# swd.net
KiCad netlist of a schematic drawn in Altium Designer
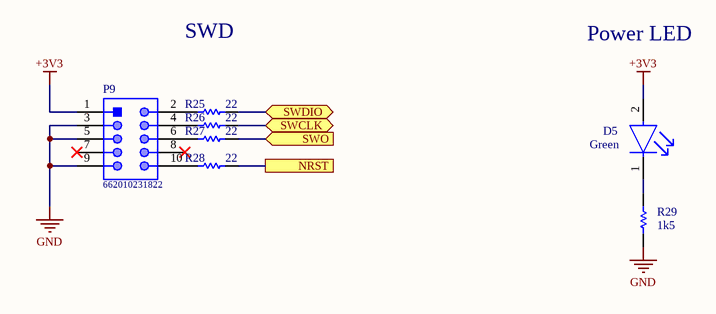
[diagram p0: swd.SchDoc]

(export (version "E")
  (design (tool "Eeschema 10.0.6"))
  (components
    (comp (ref "D5")
      (value "Green")
      (footprint "Led 0603")
      (description "LED 0805")
      (fields (field (name "VOLTAGE") "2V") (field (name "MANUFACTURER") "Vishay Lite-On"))
      (libsource (lib "F4_Flight_Controller") (part "LED 0805"))
    )
    (comp (ref "P9")
      (value "662010231822")
      (footprint "HDRV10W90P254_2X5_1270X483X840P")
      (description "SMT Male Header WR-MPC3, with SMT Solder Tabs, Vertical, Dual Row, pitch 3 mm, 10 pins")
      (fields (field (name "MANUFACTURER") "Wurth Electronics") (field (name "PUBLISHER") "WurthElektronik"))
      (libsource (lib "F4_Flight_Controller") (part "Male Header 02x05"))
    )
    (comp (ref "R25")
      (value "22")
      (footprint "Resistor 0402")
      (description "Chip Resistor 0402")
      (fields (field (name "MANUFACTURER") "Vishay") (field (name "PART NUMBER") "CRCW0402120RFKED"))
      (libsource (lib "F4_Flight_Controller") (part "Resistor 0402"))
    )
    (comp (ref "R26")
      (value "22")
      (footprint "Resistor 0402")
      (description "Chip Resistor 0402")
      (fields (field (name "MANUFACTURER") "Vishay") (field (name "PART NUMBER") "CRCW0402120RFKED"))
      (libsource (lib "F4_Flight_Controller") (part "Resistor 0402"))
    )
    (comp (ref "R27")
      (value "22")
      (footprint "Resistor 0402")
      (description "Chip Resistor 0402")
      (fields (field (name "MANUFACTURER") "Vishay") (field (name "PART NUMBER") "CRCW0402120RFKED"))
      (libsource (lib "F4_Flight_Controller") (part "Resistor 0402"))
    )
    (comp (ref "R28")
      (value "22")
      (footprint "Resistor 0402")
      (description "Chip Resistor 0402")
      (fields (field (name "MANUFACTURER") "Vishay") (field (name "PART NUMBER") "CRCW0402120RFKED"))
      (libsource (lib "F4_Flight_Controller") (part "Resistor 0402"))
    )
    (comp (ref "R29")
      (value "1k5")
      (footprint "RESISTOR 0603")
      (description "Chip Resistor 0603")
      (fields (field (name "MANUFACTURER") "Vishay") (field (name "PART NUMBER") "CRCW0402120RFKED"))
      (libsource (lib "F4_Flight_Controller") (part "Resistor 0603"))
    )
  )
  (nets
    (net (code "1") (name "+3V3") (class "Default")
      (node (ref "D5") (pin "2") (pinfunction "A_2") (pintype "passive"))
      (node (ref "P9") (pin "1") (pinfunction "1_1") (pintype "passive"))
    )
    (net (code "2") (name "/NRST") (class "Default")
      (node (ref "R28") (pin "1") (pinfunction "1_1") (pintype "passive"))
    )
    (net (code "3") (name "/SWCLK") (class "Default")
      (node (ref "R26") (pin "1") (pinfunction "1_1") (pintype "passive"))
    )
    (net (code "4") (name "/SWDIO") (class "Default")
      (node (ref "R25") (pin "1") (pinfunction "1_1") (pintype "passive"))
    )
    (net (code "5") (name "/SWO") (class "Default")
      (node (ref "R27") (pin "1") (pinfunction "1_1") (pintype "passive"))
    )
    (net (code "6") (name "GND") (class "Default")
      (node (ref "P9") (pin "3") (pinfunction "3_3") (pintype "passive"))
      (node (ref "P9") (pin "5") (pinfunction "5_5") (pintype "passive"))
      (node (ref "P9") (pin "9") (pinfunction "9_9") (pintype "passive"))
      (node (ref "R29") (pin "1") (pinfunction "1_1") (pintype "passive"))
    )
    (net (code "7") (name "Net-(D5-C)") (class "Default")
      (node (ref "D5") (pin "1") (pinfunction "C_1") (pintype "passive"))
      (node (ref "R29") (pin "2") (pinfunction "2_2") (pintype "passive"))
    )
    (net (code "8") (name "Net-(P9-Pad2)") (class "Default")
      (node (ref "P9") (pin "2") (pinfunction "2_2") (pintype "passive"))
      (node (ref "R25") (pin "2") (pinfunction "2_2") (pintype "passive"))
    )
    (net (code "9") (name "Net-(P9-Pad4)") (class "Default")
      (node (ref "P9") (pin "4") (pinfunction "4_4") (pintype "passive"))
      (node (ref "R26") (pin "2") (pinfunction "2_2") (pintype "passive"))
    )
    (net (code "10") (name "Net-(P9-Pad6)") (class "Default")
      (node (ref "P9") (pin "6") (pinfunction "6_6") (pintype "passive"))
      (node (ref "R27") (pin "2") (pinfunction "2_2") (pintype "passive"))
    )
    (net (code "11") (name "Net-(P9-Pad10)") (class "Default")
      (node (ref "P9") (pin "10") (pinfunction "10_10") (pintype "passive"))
      (node (ref "R28") (pin "2") (pinfunction "2_2") (pintype "passive"))
    )
    (net (code "12") (name "unconnected-(P9-Pad7)") (class "Default")
      (node (ref "P9") (pin "7") (pinfunction "7_7") (pintype "passive+no_connect"))
    )
    (net (code "13") (name "unconnected-(P9-Pad8)") (class "Default")
      (node (ref "P9") (pin "8") (pinfunction "8_8") (pintype "passive+no_connect"))
    )
  )
)
